# FPGA_Schematic.net
KiCad netlist of a schematic drawn in Altium Designer
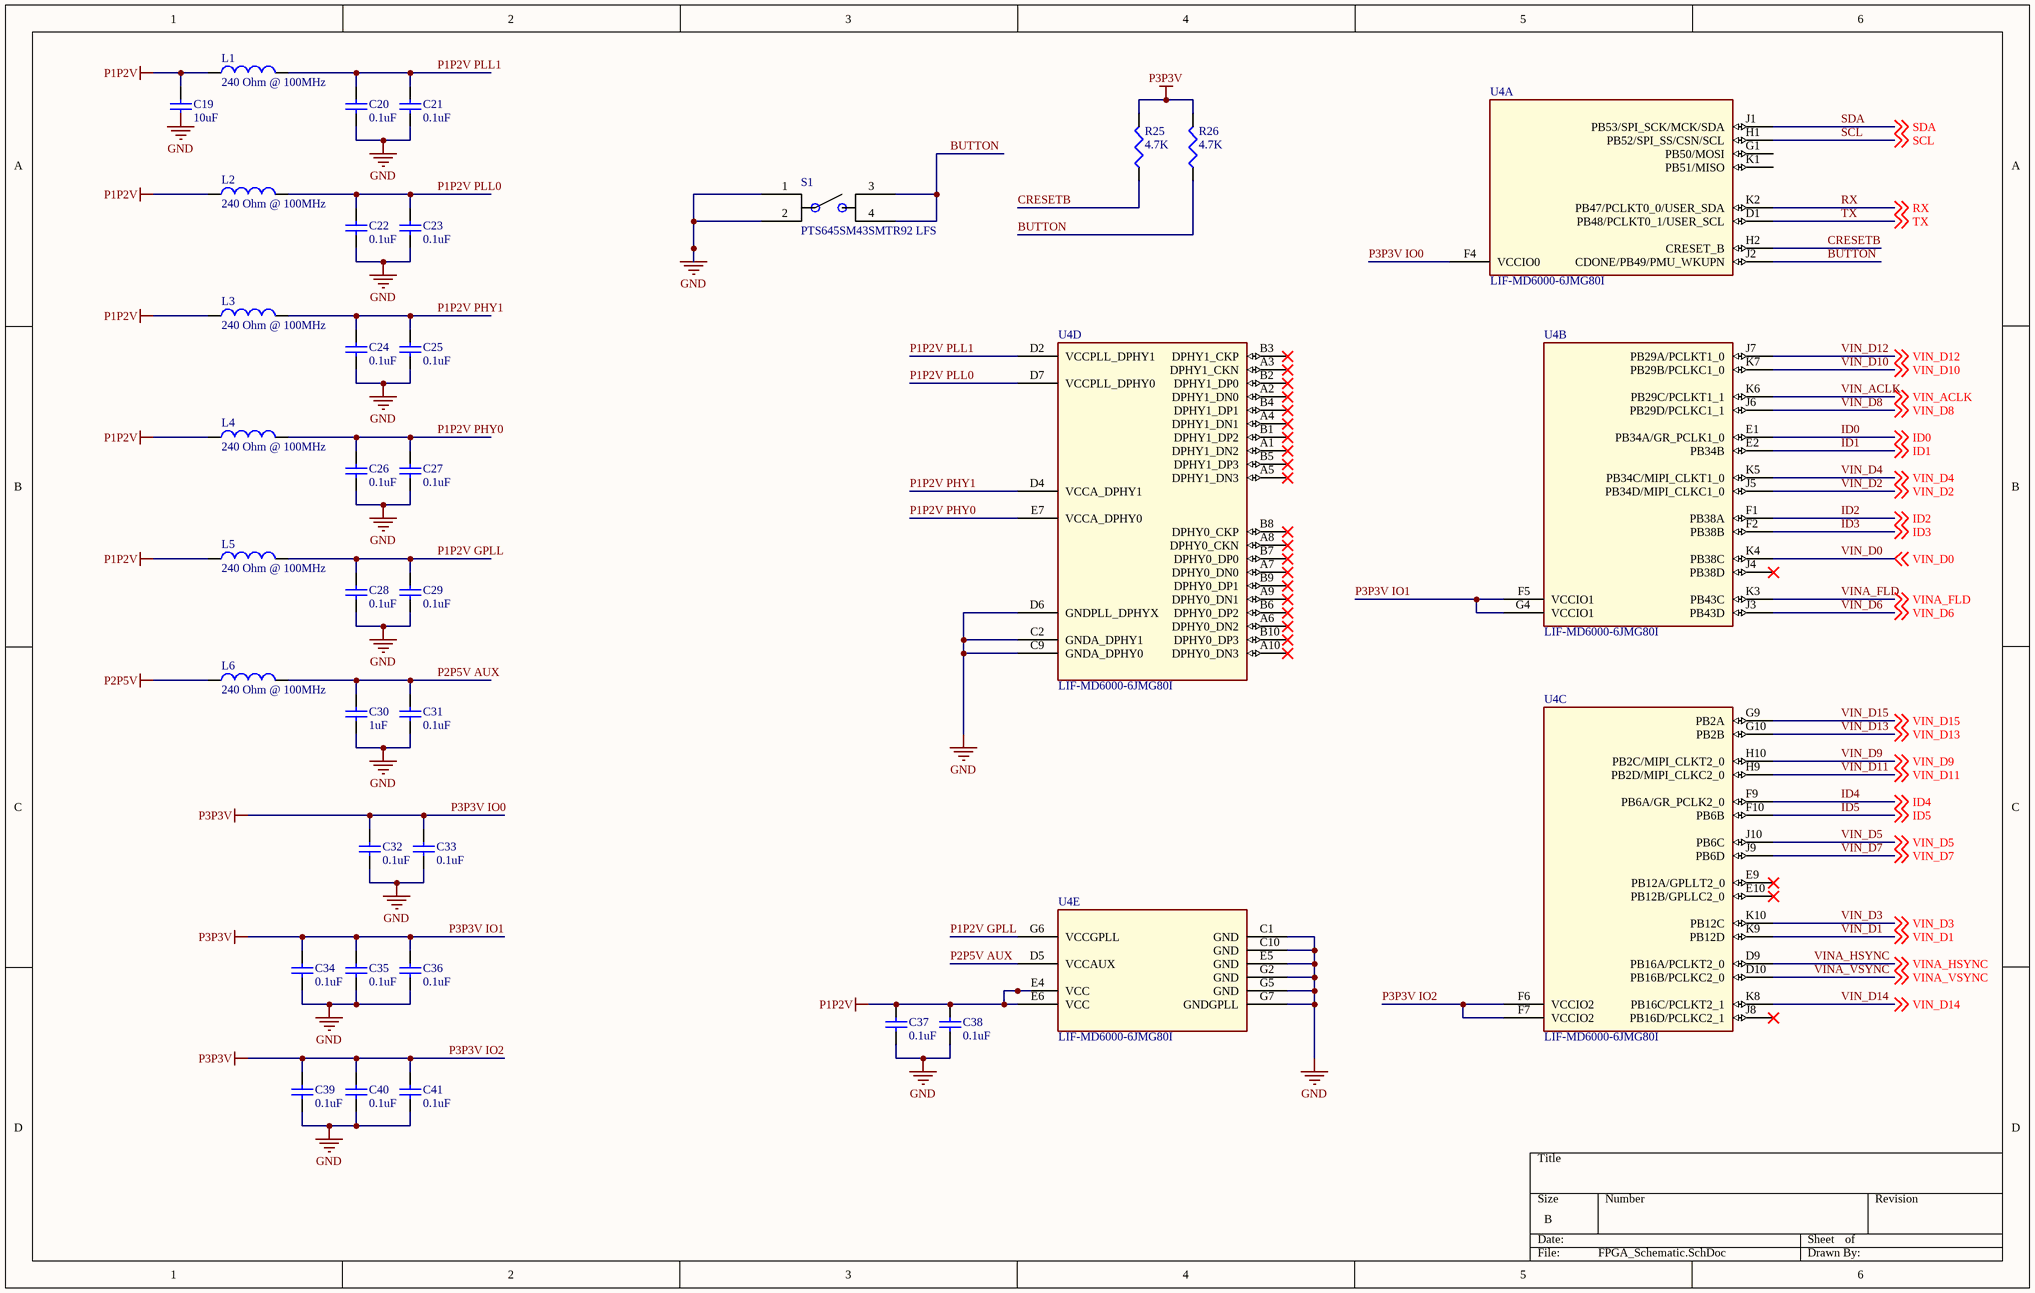
[diagram p0: FPGA_Schematic.SchDoc]

(export (version "E")
  (design (tool "Eeschema 10.0.6"))
  (components
    (comp (ref "C19")
      (value "10uF")
      (footprint "CAPC0603X33N")
      (description "CAP CER 10UF 6.3V X5R 0402")
      (fields (field (name "MFGPARTNO") "GRM155R60J106ME47D") (field (name "MFG") "Murata"))
      (libsource (lib "SLA3000-FPGA[4086]") (part "CMP-00647-A.1"))
    )
    (comp (ref "C20")
      (value "0.1uF")
      (footprint "CAPC0603X33N")
      (description "CAP CER 0.1UF 25V X7R 0402")
      (fields (field (name "SLA PART NO") "SL00150") (field (name "MFG") "TDK"))
      (libsource (lib "SLA3000-FPGA[4086]") (part "CMP-00496-A.6"))
    )
    (comp (ref "C21")
      (value "0.1uF")
      (footprint "CAPC0603X33N")
      (description "CAP CER 0.1UF 25V X7R 0402")
      (fields (field (name "SLA PART NO") "SL00150") (field (name "MFG") "TDK"))
      (libsource (lib "SLA3000-FPGA[4086]") (part "CMP-00496-A.6"))
    )
    (comp (ref "C22")
      (value "0.1uF")
      (footprint "CAPC0603X33N")
      (description "CAP CER 0.1UF 25V X7R 0402")
      (fields (field (name "SLA PART NO") "SL00150") (field (name "MFG") "TDK"))
      (libsource (lib "SLA3000-FPGA[4086]") (part "CMP-00496-A.6"))
    )
    (comp (ref "C23")
      (value "0.1uF")
      (footprint "CAPC0603X33N")
      (description "CAP CER 0.1UF 25V X7R 0402")
      (fields (field (name "SLA PART NO") "SL00150") (field (name "MFG") "TDK"))
      (libsource (lib "SLA3000-FPGA[4086]") (part "CMP-00496-A.6"))
    )
    (comp (ref "C24")
      (value "0.1uF")
      (footprint "CAPC0603X33N")
      (description "CAP CER 0.1UF 25V X7R 0402")
      (fields (field (name "SLA PART NO") "SL00150") (field (name "MFG") "TDK"))
      (libsource (lib "SLA3000-FPGA[4086]") (part "CMP-00496-A.6"))
    )
    (comp (ref "C25")
      (value "0.1uF")
      (footprint "CAPC0603X33N")
      (description "CAP CER 0.1UF 25V X7R 0402")
      (fields (field (name "SLA PART NO") "SL00150") (field (name "MFG") "TDK"))
      (libsource (lib "SLA3000-FPGA[4086]") (part "CMP-00496-A.6"))
    )
    (comp (ref "C26")
      (value "0.1uF")
      (footprint "CAPC0603X33N")
      (description "CAP CER 0.1UF 25V X7R 0402")
      (fields (field (name "SLA PART NO") "SL00150") (field (name "MFG") "TDK"))
      (libsource (lib "SLA3000-FPGA[4086]") (part "CMP-00496-A.6"))
    )
    (comp (ref "C27")
      (value "0.1uF")
      (footprint "CAPC0603X33N")
      (description "CAP CER 0.1UF 25V X7R 0402")
      (fields (field (name "SLA PART NO") "SL00150") (field (name "MFG") "TDK"))
      (libsource (lib "SLA3000-FPGA[4086]") (part "CMP-00496-A.6"))
    )
    (comp (ref "C28")
      (value "0.1uF")
      (footprint "CAPC0603X33N")
      (description "CAP CER 0.1UF 25V X7R 0402")
      (fields (field (name "SLA PART NO") "SL00150") (field (name "MFG") "TDK"))
      (libsource (lib "SLA3000-FPGA[4086]") (part "CMP-00496-A.6"))
    )
    (comp (ref "C29")
      (value "0.1uF")
      (footprint "CAPC0603X33N")
      (description "CAP CER 0.1UF 25V X7R 0402")
      (fields (field (name "SLA PART NO") "SL00150") (field (name "MFG") "TDK"))
      (libsource (lib "SLA3000-FPGA[4086]") (part "CMP-00496-A.6"))
    )
    (comp (ref "C30")
      (value "1uF")
      (footprint "CAPC0603X33N")
      (description "CAP CER 1UF 25V X5R 0402")
      (fields (field (name "MFGPARTNO") "EMK105BJ105KV-F") (field (name "MFG") "Taiyo Yuden"))
      (libsource (lib "SLA3000-FPGA[4086]") (part "CMP-00695-A.2"))
    )
    (comp (ref "C31")
      (value "0.1uF")
      (footprint "CAPC0603X33N")
      (description "CAP CER 0.1UF 25V X7R 0402")
      (fields (field (name "SLA PART NO") "SL00150") (field (name "MFG") "TDK"))
      (libsource (lib "SLA3000-FPGA[4086]") (part "CMP-00496-A.6"))
    )
    (comp (ref "C32")
      (value "0.1uF")
      (footprint "CAPC0603X33N")
      (description "CAP CER 0.1UF 25V X7R 0402")
      (fields (field (name "SLA PART NO") "SL00150") (field (name "MFG") "TDK"))
      (libsource (lib "SLA3000-FPGA[4086]") (part "CMP-00496-A.6"))
    )
    (comp (ref "C33")
      (value "0.1uF")
      (footprint "CAPC0603X33N")
      (description "CAP CER 0.1UF 25V X7R 0402")
      (fields (field (name "SLA PART NO") "SL00150") (field (name "MFG") "TDK"))
      (libsource (lib "SLA3000-FPGA[4086]") (part "CMP-00496-A.6"))
    )
    (comp (ref "C34")
      (value "0.1uF")
      (footprint "CAPC0603X33N")
      (description "CAP CER 0.1UF 25V X7R 0402")
      (fields (field (name "SLA PART NO") "SL00150") (field (name "MFG") "TDK"))
      (libsource (lib "SLA3000-FPGA[4086]") (part "CMP-00496-A.6"))
    )
    (comp (ref "C35")
      (value "0.1uF")
      (footprint "CAPC0603X33N")
      (description "CAP CER 0.1UF 25V X7R 0402")
      (fields (field (name "SLA PART NO") "SL00150") (field (name "MFG") "TDK"))
      (libsource (lib "SLA3000-FPGA[4086]") (part "CMP-00496-A.6"))
    )
    (comp (ref "C36")
      (value "0.1uF")
      (footprint "CAPC0603X33N")
      (description "CAP CER 0.1UF 25V X7R 0402")
      (fields (field (name "SLA PART NO") "SL00150") (field (name "MFG") "TDK"))
      (libsource (lib "SLA3000-FPGA[4086]") (part "CMP-00496-A.6"))
    )
    (comp (ref "C37")
      (value "0.1uF")
      (footprint "INDC1005X45")
      (description "CAP CER 0.1UF 25V X7R 0402")
      (fields (field (name "SLA PART NO") "SL00150") (field (name "MFG") "TDK"))
      (libsource (lib "SLA3000-FPGA[4086]") (part "CMP-00496-A.6"))
    )
    (comp (ref "C38")
      (value "0.1uF")
      (footprint "INDC1005X45")
      (description "CAP CER 0.1UF 25V X7R 0402")
      (fields (field (name "SLA PART NO") "SL00150") (field (name "MFG") "TDK"))
      (libsource (lib "SLA3000-FPGA[4086]") (part "CMP-00496-A.6"))
    )
    (comp (ref "C39")
      (value "0.1uF")
      (footprint "CAPC0603X33N")
      (description "CAP CER 0.1UF 25V X7R 0402")
      (fields (field (name "SLA PART NO") "SL00150") (field (name "MFG") "TDK"))
      (libsource (lib "SLA3000-FPGA[4086]") (part "CMP-00496-A.6"))
    )
    (comp (ref "C40")
      (value "0.1uF")
      (footprint "CAPC0603X33N")
      (description "CAP CER 0.1UF 25V X7R 0402")
      (fields (field (name "SLA PART NO") "SL00150") (field (name "MFG") "TDK"))
      (libsource (lib "SLA3000-FPGA[4086]") (part "CMP-00496-A.6"))
    )
    (comp (ref "C41")
      (value "0.1uF")
      (footprint "CAPC0603X33N")
      (description "CAP CER 0.1UF 25V X7R 0402")
      (fields (field (name "SLA PART NO") "SL00150") (field (name "MFG") "TDK"))
      (libsource (lib "SLA3000-FPGA[4086]") (part "CMP-00496-A.6"))
    )
    (comp (ref "L1")
      (value "240 Ohm @ 100MHz")
      (footprint "IND_LQP03HQ4N5J02D")
      (description "BLM03BD241SN1D FERRITE BEAD 240 OHM 0201 1LN")
      (fields (field (name "MFG") "Murata") (field (name "MFGPARTNO") "BLM03BD241SN1D"))
      (libsource (lib "SLA3000-FPGA[4086]") (part "CMP-00665-A.1"))
    )
    (comp (ref "L2")
      (value "240 Ohm @ 100MHz")
      (footprint "IND_LQP03HQ4N5J02D")
      (description "BLM03BD241SN1D FERRITE BEAD 240 OHM 0201 1LN")
      (fields (field (name "MFG") "Murata") (field (name "MFGPARTNO") "BLM03BD241SN1D"))
      (libsource (lib "SLA3000-FPGA[4086]") (part "CMP-00665-A.1"))
    )
    (comp (ref "L3")
      (value "240 Ohm @ 100MHz")
      (footprint "IND_LQP03HQ4N5J02D")
      (description "BLM03BD241SN1D FERRITE BEAD 240 OHM 0201 1LN")
      (fields (field (name "MFG") "Murata") (field (name "MFGPARTNO") "BLM03BD241SN1D"))
      (libsource (lib "SLA3000-FPGA[4086]") (part "CMP-00665-A.1"))
    )
    (comp (ref "L4")
      (value "240 Ohm @ 100MHz")
      (footprint "IND_LQP03HQ4N5J02D")
      (description "BLM03BD241SN1D FERRITE BEAD 240 OHM 0201 1LN")
      (fields (field (name "MFG") "Murata") (field (name "MFGPARTNO") "BLM03BD241SN1D"))
      (libsource (lib "SLA3000-FPGA[4086]") (part "CMP-00665-A.1"))
    )
    (comp (ref "L5")
      (value "240 Ohm @ 100MHz")
      (footprint "IND_LQP03HQ4N5J02D")
      (description "BLM03BD241SN1D FERRITE BEAD 240 OHM 0201 1LN")
      (fields (field (name "MFG") "Murata") (field (name "MFGPARTNO") "BLM03BD241SN1D"))
      (libsource (lib "SLA3000-FPGA[4086]") (part "CMP-00665-A.1"))
    )
    (comp (ref "L6")
      (value "240 Ohm @ 100MHz")
      (footprint "IND_LQP03HQ4N5J02D")
      (description "BLM03BD241SN1D FERRITE BEAD 240 OHM 0201 1LN")
      (fields (field (name "MFG") "Murata") (field (name "MFGPARTNO") "BLM03BD241SN1D"))
      (libsource (lib "SLA3000-FPGA[4086]") (part "CMP-00665-A.1"))
    )
    (comp (ref "R25")
      (value "4.7K")
      (footprint "RES_ERJU02F1241X")
      (description "RES SMD 4K7 OHM 1% 1/16W 0402")
      (fields (field (name "MFGPARTNO") "RC0402FR-074K7P") (field (name "MFG") "Yageo"))
      (libsource (lib "SLA3000-FPGA[4086]") (part "CMP-00761-A.1"))
    )
    (comp (ref "R26")
      (value "4.7K")
      (footprint "RES_ERJU02F1241X")
      (description "RES SMD 4K7 OHM 1% 1/16W 0402")
      (fields (field (name "MFGPARTNO") "RC0402FR-074K7P") (field (name "MFG") "Yageo"))
      (libsource (lib "SLA3000-FPGA[4086]") (part "CMP-00761-A.1"))
    )
    (comp (ref "S1")
      (value "PTS645SM43SMTR92 LFS")
      (footprint "SWITCH_43SMTR92LFS")
      (description "PTS645SM43SMTR92 LFS SWITCH TACTILE SPST-NO 0.05A 12V")
      (fields (field (name "MFG") "C&K"))
      (libsource (lib "SLA3000-FPGA[4086]") (part "CMP-00660-2"))
    )
    (comp (ref "U4")
      (value "LIF-MD6000-6JMG80I")
      (footprint "BGA80C65P10X10_650X650X100N")
      (description "LIF-MD6000-6JMG80I LATTICE CROSSLINK - INTERFACE MIPI D-")
      (fields (field (name "MFG") "Lattice"))
      (libsource (lib "SLA3000-FPGA[4086]") (part "CMP-00644-A.1"))
    )
  )
  (nets
    (net (code "1") (name "/BUTTON") (class "Default")
      (node (ref "R26") (pin "1") (pinfunction "1_1") (pintype "passive"))
      (node (ref "S1") (pin "3") (pinfunction "3_3") (pintype "passive"))
      (node (ref "S1") (pin "4") (pinfunction "4_4") (pintype "passive"))
      (node (ref "U4") (pin "J2") (pinfunction "CDONE/PB49/PMU_WKUPN_J2") (pintype "bidirectional"))
    )
    (net (code "2") (name "/CRESETB") (class "Default")
      (node (ref "R25") (pin "1") (pinfunction "1_1") (pintype "passive"))
      (node (ref "U4") (pin "H2") (pinfunction "CRESET_B_H2") (pintype "bidirectional"))
    )
    (net (code "3") (name "/P1P2V GPLL") (class "Default")
      (node (ref "C28") (pin "2") (pinfunction "2_2") (pintype "passive"))
      (node (ref "C29") (pin "2") (pinfunction "2_2") (pintype "passive"))
      (node (ref "L5") (pin "2") (pinfunction "2_2") (pintype "passive"))
      (node (ref "U4") (pin "G6") (pinfunction "VCCGPLL_G6") (pintype "power_in"))
    )
    (net (code "4") (name "/P1P2V PHY0") (class "Default")
      (node (ref "C26") (pin "2") (pinfunction "2_2") (pintype "passive"))
      (node (ref "C27") (pin "2") (pinfunction "2_2") (pintype "passive"))
      (node (ref "L4") (pin "2") (pinfunction "2_2") (pintype "passive"))
      (node (ref "U4") (pin "E7") (pinfunction "VCCA_DPHY0_E7") (pintype "power_in"))
    )
    (net (code "5") (name "/P1P2V PHY1") (class "Default")
      (node (ref "C24") (pin "2") (pinfunction "2_2") (pintype "passive"))
      (node (ref "C25") (pin "2") (pinfunction "2_2") (pintype "passive"))
      (node (ref "L3") (pin "2") (pinfunction "2_2") (pintype "passive"))
      (node (ref "U4") (pin "D4") (pinfunction "VCCA_DPHY1_D4") (pintype "power_in"))
    )
    (net (code "6") (name "/P1P2V PLL0") (class "Default")
      (node (ref "C22") (pin "2") (pinfunction "2_2") (pintype "passive"))
      (node (ref "C23") (pin "2") (pinfunction "2_2") (pintype "passive"))
      (node (ref "L2") (pin "2") (pinfunction "2_2") (pintype "passive"))
      (node (ref "U4") (pin "D7") (pinfunction "VCCPLL_DPHY0_D7") (pintype "power_in"))
    )
    (net (code "7") (name "/P1P2V PLL1") (class "Default")
      (node (ref "C20") (pin "2") (pinfunction "2_2") (pintype "passive"))
      (node (ref "C21") (pin "2") (pinfunction "2_2") (pintype "passive"))
      (node (ref "L1") (pin "2") (pinfunction "2_2") (pintype "passive"))
      (node (ref "U4") (pin "D2") (pinfunction "VCCPLL_DPHY1_D2") (pintype "power_in"))
    )
    (net (code "8") (name "/P2P5V AUX") (class "Default")
      (node (ref "C30") (pin "2") (pinfunction "2_2") (pintype "passive"))
      (node (ref "C31") (pin "2") (pinfunction "2_2") (pintype "passive"))
      (node (ref "L6") (pin "2") (pinfunction "2_2") (pintype "passive"))
      (node (ref "U4") (pin "D5") (pinfunction "VCCAUX_D5") (pintype "power_in"))
    )
    (net (code "9") (name "GND") (class "Default")
      (node (ref "C20") (pin "1") (pinfunction "1_1") (pintype "passive"))
      (node (ref "C21") (pin "1") (pinfunction "1_1") (pintype "passive"))
      (node (ref "C22") (pin "1") (pinfunction "1_1") (pintype "passive"))
      (node (ref "C23") (pin "1") (pinfunction "1_1") (pintype "passive"))
      (node (ref "C24") (pin "1") (pinfunction "1_1") (pintype "passive"))
      (node (ref "C25") (pin "1") (pinfunction "1_1") (pintype "passive"))
      (node (ref "C26") (pin "1") (pinfunction "1_1") (pintype "passive"))
      (node (ref "C27") (pin "1") (pinfunction "1_1") (pintype "passive"))
      (node (ref "C28") (pin "1") (pinfunction "1_1") (pintype "passive"))
      (node (ref "C29") (pin "1") (pinfunction "1_1") (pintype "passive"))
      (node (ref "C30") (pin "1") (pinfunction "1_1") (pintype "passive"))
      (node (ref "C31") (pin "1") (pinfunction "1_1") (pintype "passive"))
      (node (ref "C32") (pin "1") (pinfunction "1_1") (pintype "passive"))
      (node (ref "C33") (pin "1") (pinfunction "1_1") (pintype "passive"))
      (node (ref "C34") (pin "1") (pinfunction "1_1") (pintype "passive"))
      (node (ref "C35") (pin "1") (pinfunction "1_1") (pintype "passive"))
      (node (ref "C36") (pin "1") (pinfunction "1_1") (pintype "passive"))
      (node (ref "C37") (pin "1") (pinfunction "1_1") (pintype "passive"))
      (node (ref "C38") (pin "1") (pinfunction "1_1") (pintype "passive"))
      (node (ref "C39") (pin "1") (pinfunction "1_1") (pintype "passive"))
      (node (ref "C40") (pin "1") (pinfunction "1_1") (pintype "passive"))
      (node (ref "C41") (pin "1") (pinfunction "1_1") (pintype "passive"))
      (node (ref "S1") (pin "1") (pinfunction "1_1") (pintype "passive"))
      (node (ref "S1") (pin "2") (pinfunction "2_2") (pintype "passive"))
      (node (ref "U4") (pin "C1") (pinfunction "GND_C1") (pintype "power_in"))
      (node (ref "U4") (pin "C10") (pinfunction "GND_C10") (pintype "power_in"))
      (node (ref "U4") (pin "C2") (pinfunction "GNDA_DPHY1_C2") (pintype "power_in"))
      (node (ref "U4") (pin "C9") (pinfunction "GNDA_DPHY0_C9") (pintype "power_in"))
      (node (ref "U4") (pin "D6") (pinfunction "GNDPLL_DPHYX_D6") (pintype "power_in"))
      (node (ref "U4") (pin "E5") (pinfunction "GND_E5") (pintype "power_in"))
      (node (ref "U4") (pin "G2") (pinfunction "GND_G2") (pintype "power_in"))
      (node (ref "U4") (pin "G5") (pinfunction "GND_G5") (pintype "power_in"))
      (node (ref "U4") (pin "G7") (pinfunction "GNDGPLL_G7") (pintype "power_in"))
    )
    (net (code "10") (name "ID0") (class "Default")
      (node (ref "U4") (pin "E1") (pinfunction "PB34A/GR_PCLK1_0_E1") (pintype "bidirectional"))
    )
    (net (code "11") (name "ID1") (class "Default")
      (node (ref "U4") (pin "E2") (pinfunction "PB34B_E2") (pintype "bidirectional"))
    )
    (net (code "12") (name "ID2") (class "Default")
      (node (ref "U4") (pin "F1") (pinfunction "PB38A_F1") (pintype "bidirectional"))
    )
    (net (code "13") (name "ID3") (class "Default")
      (node (ref "U4") (pin "F2") (pinfunction "PB38B_F2") (pintype "bidirectional"))
    )
    (net (code "14") (name "ID4") (class "Default")
      (node (ref "U4") (pin "F9") (pinfunction "PB6A/GR_PCLK2_0_F9") (pintype "bidirectional"))
    )
    (net (code "15") (name "ID5") (class "Default")
      (node (ref "U4") (pin "F10") (pinfunction "PB6B_F10") (pintype "bidirectional"))
    )
    (net (code "16") (name "P1P2V") (class "Default")
      (node (ref "C19") (pin "2") (pinfunction "2_2") (pintype "passive"))
      (node (ref "C37") (pin "2") (pinfunction "2_2") (pintype "passive"))
      (node (ref "C38") (pin "2") (pinfunction "2_2") (pintype "passive"))
      (node (ref "L1") (pin "1") (pinfunction "1_1") (pintype "passive"))
      (node (ref "L2") (pin "1") (pinfunction "1_1") (pintype "passive"))
      (node (ref "L3") (pin "1") (pinfunction "1_1") (pintype "passive"))
      (node (ref "L4") (pin "1") (pinfunction "1_1") (pintype "passive"))
      (node (ref "L5") (pin "1") (pinfunction "1_1") (pintype "passive"))
      (node (ref "U4") (pin "E4") (pinfunction "VCC_E4") (pintype "power_in"))
      (node (ref "U4") (pin "E6") (pinfunction "VCC_E6") (pintype "power_in"))
    )
    (net (code "17") (name "P2P5V") (class "Default")
      (node (ref "L6") (pin "1") (pinfunction "1_1") (pintype "passive"))
    )
    (net (code "18") (name "P3P3V") (class "Default")
      (node (ref "C32") (pin "2") (pinfunction "2_2") (pintype "passive"))
      (node (ref "C33") (pin "2") (pinfunction "2_2") (pintype "passive"))
      (node (ref "C34") (pin "2") (pinfunction "2_2") (pintype "passive"))
      (node (ref "C35") (pin "2") (pinfunction "2_2") (pintype "passive"))
      (node (ref "C36") (pin "2") (pinfunction "2_2") (pintype "passive"))
      (node (ref "C39") (pin "2") (pinfunction "2_2") (pintype "passive"))
      (node (ref "C40") (pin "2") (pinfunction "2_2") (pintype "passive"))
      (node (ref "C41") (pin "2") (pinfunction "2_2") (pintype "passive"))
      (node (ref "R25") (pin "2") (pinfunction "2_2") (pintype "passive"))
      (node (ref "R26") (pin "2") (pinfunction "2_2") (pintype "passive"))
      (node (ref "U4") (pin "F4") (pinfunction "VCCIO0_F4") (pintype "power_in"))
      (node (ref "U4") (pin "F5") (pinfunction "VCCIO1_F5") (pintype "power_in"))
      (node (ref "U4") (pin "F6") (pinfunction "VCCIO2_F6") (pintype "power_in"))
      (node (ref "U4") (pin "F7") (pinfunction "VCCIO2_F7") (pintype "power_in"))
      (node (ref "U4") (pin "G4") (pinfunction "VCCIO1_G4") (pintype "power_in"))
    )
    (net (code "19") (name "RX") (class "Default")
      (node (ref "U4") (pin "K2") (pinfunction "PB47/PCLKT0_0/USER_SDA_K2") (pintype "bidirectional"))
    )
    (net (code "20") (name "SCL") (class "Default")
      (node (ref "U4") (pin "H1") (pinfunction "PB52/SPI_SS/CSN/SCL_H1") (pintype "bidirectional"))
    )
    (net (code "21") (name "SDA") (class "Default")
      (node (ref "U4") (pin "J1") (pinfunction "PB53/SPI_SCK/MCK/SDA_J1") (pintype "bidirectional"))
    )
    (net (code "22") (name "TX") (class "Default")
      (node (ref "U4") (pin "D1") (pinfunction "PB48/PCLKT0_1/USER_SCL_D1") (pintype "bidirectional"))
    )
    (net (code "23") (name "VINA_FLD") (class "Default")
      (node (ref "U4") (pin "K3") (pinfunction "PB43C_K3") (pintype "bidirectional"))
    )
    (net (code "24") (name "VINA_HSYNC") (class "Default")
      (node (ref "U4") (pin "D9") (pinfunction "PB16A/PCLKT2_0_D9") (pintype "bidirectional"))
    )
    (net (code "25") (name "VINA_VSYNC") (class "Default")
      (node (ref "U4") (pin "D10") (pinfunction "PB16B/PCLKC2_0_D10") (pintype "bidirectional"))
    )
    (net (code "26") (name "VIN_ACLK") (class "Default")
      (node (ref "U4") (pin "K6") (pinfunction "PB29C/PCLKT1_1_K6") (pintype "bidirectional"))
    )
    (net (code "27") (name "VIN_D0") (class "Default")
      (node (ref "U4") (pin "K4") (pinfunction "PB38C_K4") (pintype "bidirectional"))
    )
    (net (code "28") (name "VIN_D1") (class "Default")
      (node (ref "U4") (pin "K9") (pinfunction "PB12D_K9") (pintype "bidirectional"))
    )
    (net (code "29") (name "VIN_D2") (class "Default")
      (node (ref "U4") (pin "J5") (pinfunction "PB34D/MIPI_CLKC1_0_J5") (pintype "bidirectional"))
    )
    (net (code "30") (name "VIN_D3") (class "Default")
      (node (ref "U4") (pin "K10") (pinfunction "PB12C_K10") (pintype "bidirectional"))
    )
    (net (code "31") (name "VIN_D4") (class "Default")
      (node (ref "U4") (pin "K5") (pinfunction "PB34C/MIPI_CLKT1_0_K5") (pintype "bidirectional"))
    )
    (net (code "32") (name "VIN_D5") (class "Default")
      (node (ref "U4") (pin "J10") (pinfunction "PB6C_J10") (pintype "bidirectional"))
    )
    (net (code "33") (name "VIN_D6") (class "Default")
      (node (ref "U4") (pin "J3") (pinfunction "PB43D_J3") (pintype "bidirectional"))
    )
    (net (code "34") (name "VIN_D7") (class "Default")
      (node (ref "U4") (pin "J9") (pinfunction "PB6D_J9") (pintype "bidirectional"))
    )
    (net (code "35") (name "VIN_D8") (class "Default")
      (node (ref "U4") (pin "J6") (pinfunction "PB29D/PCLKC1_1_J6") (pintype "bidirectional"))
    )
    (net (code "36") (name "VIN_D9") (class "Default")
      (node (ref "U4") (pin "H10") (pinfunction "PB2C/MIPI_CLKT2_0_H10") (pintype "bidirectional"))
    )
    (net (code "37") (name "VIN_D10") (class "Default")
      (node (ref "U4") (pin "K7") (pinfunction "PB29B/PCLKC1_0_K7") (pintype "bidirectional"))
    )
    (net (code "38") (name "VIN_D11") (class "Default")
      (node (ref "U4") (pin "H9") (pinfunction "PB2D/MIPI_CLKC2_0_H9") (pintype "bidirectional"))
    )
    (net (code "39") (name "VIN_D12") (class "Default")
      (node (ref "U4") (pin "J7") (pinfunction "PB29A/PCLKT1_0_J7") (pintype "bidirectional"))
    )
    (net (code "40") (name "VIN_D13") (class "Default")
      (node (ref "U4") (pin "G10") (pinfunction "PB2B_G10") (pintype "bidirectional"))
    )
    (net (code "41") (name "VIN_D14") (class "Default")
      (node (ref "U4") (pin "K8") (pinfunction "PB16C/PCLKT2_1_K8") (pintype "bidirectional"))
    )
    (net (code "42") (name "VIN_D15") (class "Default")
      (node (ref "U4") (pin "G9") (pinfunction "PB2A_G9") (pintype "bidirectional"))
    )
    (net (code "43") (name "unconnected-(C19-Pad1)") (class "Default")
      (node (ref "C19") (pin "1") (pinfunction "1_1") (pintype "passive"))
    )
    (net (code "44") (name "unconnected-(U4A-PB50{slash}MOSI-PadG1)") (class "Default")
      (node (ref "U4") (pin "G1") (pinfunction "PB50/MOSI_G1") (pintype "bidirectional"))
    )
    (net (code "45") (name "unconnected-(U4A-PB51{slash}MISO-PadK1)") (class "Default")
      (node (ref "U4") (pin "K1") (pinfunction "PB51/MISO_K1") (pintype "bidirectional"))
    )
    (net (code "46") (name "unconnected-(U4B-PB38D-PadJ4)") (class "Default")
      (node (ref "U4") (pin "J4") (pinfunction "PB38D_J4") (pintype "bidirectional+no_connect"))
    )
    (net (code "47") (name "unconnected-(U4C-PB12A{slash}GPLLT2_0-PadE9)") (class "Default")
      (node (ref "U4") (pin "E9") (pinfunction "PB12A/GPLLT2_0_E9") (pintype "bidirectional+no_connect"))
    )
    (net (code "48") (name "unconnected-(U4C-PB12B{slash}GPLLC2_0-PadE10)") (class "Default")
      (node (ref "U4") (pin "E10") (pinfunction "PB12B/GPLLC2_0_E10") (pintype "bidirectional+no_connect"))
    )
    (net (code "49") (name "unconnected-(U4C-PB16D{slash}PCLKC2_1-PadJ8)") (class "Default")
      (node (ref "U4") (pin "J8") (pinfunction "PB16D/PCLKC2_1_J8") (pintype "bidirectional+no_connect"))
    )
    (net (code "50") (name "unconnected-(U4D-DPHY0_CKN-PadA8)") (class "Default")
      (node (ref "U4") (pin "A8") (pinfunction "DPHY0_CKN_A8") (pintype "bidirectional+no_connect"))
    )
    (net (code "51") (name "unconnected-(U4D-DPHY0_CKP-PadB8)") (class "Default")
      (node (ref "U4") (pin "B8") (pinfunction "DPHY0_CKP_B8") (pintype "bidirectional+no_connect"))
    )
    (net (code "52") (name "unconnected-(U4D-DPHY0_DN0-PadA7)") (class "Default")
      (node (ref "U4") (pin "A7") (pinfunction "DPHY0_DN0_A7") (pintype "bidirectional+no_connect"))
    )
    (net (code "53") (name "unconnected-(U4D-DPHY0_DN1-PadA9)") (class "Default")
      (node (ref "U4") (pin "A9") (pinfunction "DPHY0_DN1_A9") (pintype "bidirectional+no_connect"))
    )
    (net (code "54") (name "unconnected-(U4D-DPHY0_DN2-PadA6)") (class "Default")
      (node (ref "U4") (pin "A6") (pinfunction "DPHY0_DN2_A6") (pintype "bidirectional+no_connect"))
    )
    (net (code "55") (name "unconnected-(U4D-DPHY0_DN3-PadA10)") (class "Default")
      (node (ref "U4") (pin "A10") (pinfunction "DPHY0_DN3_A10") (pintype "bidirectional+no_connect"))
    )
    (net (code "56") (name "unconnected-(U4D-DPHY0_DP0-PadB7)") (class "Default")
      (node (ref "U4") (pin "B7") (pinfunction "DPHY0_DP0_B7") (pintype "bidirectional+no_connect"))
    )
    (net (code "57") (name "unconnected-(U4D-DPHY0_DP1-PadB9)") (class "Default")
      (node (ref "U4") (pin "B9") (pinfunction "DPHY0_DP1_B9") (pintype "bidirectional+no_connect"))
    )
    (net (code "58") (name "unconnected-(U4D-DPHY0_DP2-PadB6)") (class "Default")
      (node (ref "U4") (pin "B6") (pinfunction "DPHY0_DP2_B6") (pintype "bidirectional+no_connect"))
    )
    (net (code "59") (name "unconnected-(U4D-DPHY0_DP3-PadB10)") (class "Default")
      (node (ref "U4") (pin "B10") (pinfunction "DPHY0_DP3_B10") (pintype "bidirectional+no_connect"))
    )
    (net (code "60") (name "unconnected-(U4D-DPHY1_CKN-PadA3)") (class "Default")
      (node (ref "U4") (pin "A3") (pinfunction "DPHY1_CKN_A3") (pintype "bidirectional+no_connect"))
    )
    (net (code "61") (name "unconnected-(U4D-DPHY1_CKP-PadB3)") (class "Default")
      (node (ref "U4") (pin "B3") (pinfunction "DPHY1_CKP_B3") (pintype "bidirectional+no_connect"))
    )
    (net (code "62") (name "unconnected-(U4D-DPHY1_DN0-PadA2)") (class "Default")
      (node (ref "U4") (pin "A2") (pinfunction "DPHY1_DN0_A2") (pintype "bidirectional+no_connect"))
    )
    (net (code "63") (name "unconnected-(U4D-DPHY1_DN1-PadA4)") (class "Default")
      (node (ref "U4") (pin "A4") (pinfunction "DPHY1_DN1_A4") (pintype "bidirectional+no_connect"))
    )
    (net (code "64") (name "unconnected-(U4D-DPHY1_DN2-PadA1)") (class "Default")
      (node (ref "U4") (pin "A1") (pinfunction "DPHY1_DN2_A1") (pintype "bidirectional+no_connect"))
    )
    (net (code "65") (name "unconnected-(U4D-DPHY1_DN3-PadA5)") (class "Default")
      (node (ref "U4") (pin "A5") (pinfunction "DPHY1_DN3_A5") (pintype "bidirectional+no_connect"))
    )
    (net (code "66") (name "unconnected-(U4D-DPHY1_DP0-PadB2)") (class "Default")
      (node (ref "U4") (pin "B2") (pinfunction "DPHY1_DP0_B2") (pintype "bidirectional+no_connect"))
    )
    (net (code "67") (name "unconnected-(U4D-DPHY1_DP1-PadB4)") (class "Default")
      (node (ref "U4") (pin "B4") (pinfunction "DPHY1_DP1_B4") (pintype "bidirectional+no_connect"))
    )
    (net (code "68") (name "unconnected-(U4D-DPHY1_DP2-PadB1)") (class "Default")
      (node (ref "U4") (pin "B1") (pinfunction "DPHY1_DP2_B1") (pintype "bidirectional+no_connect"))
    )
    (net (code "69") (name "unconnected-(U4D-DPHY1_DP3-PadB5)") (class "Default")
      (node (ref "U4") (pin "B5") (pinfunction "DPHY1_DP3_B5") (pintype "bidirectional+no_connect"))
    )
  )
)
